# RoboArm_Schematic.net
KiCad netlist of a schematic drawn in EAGLE
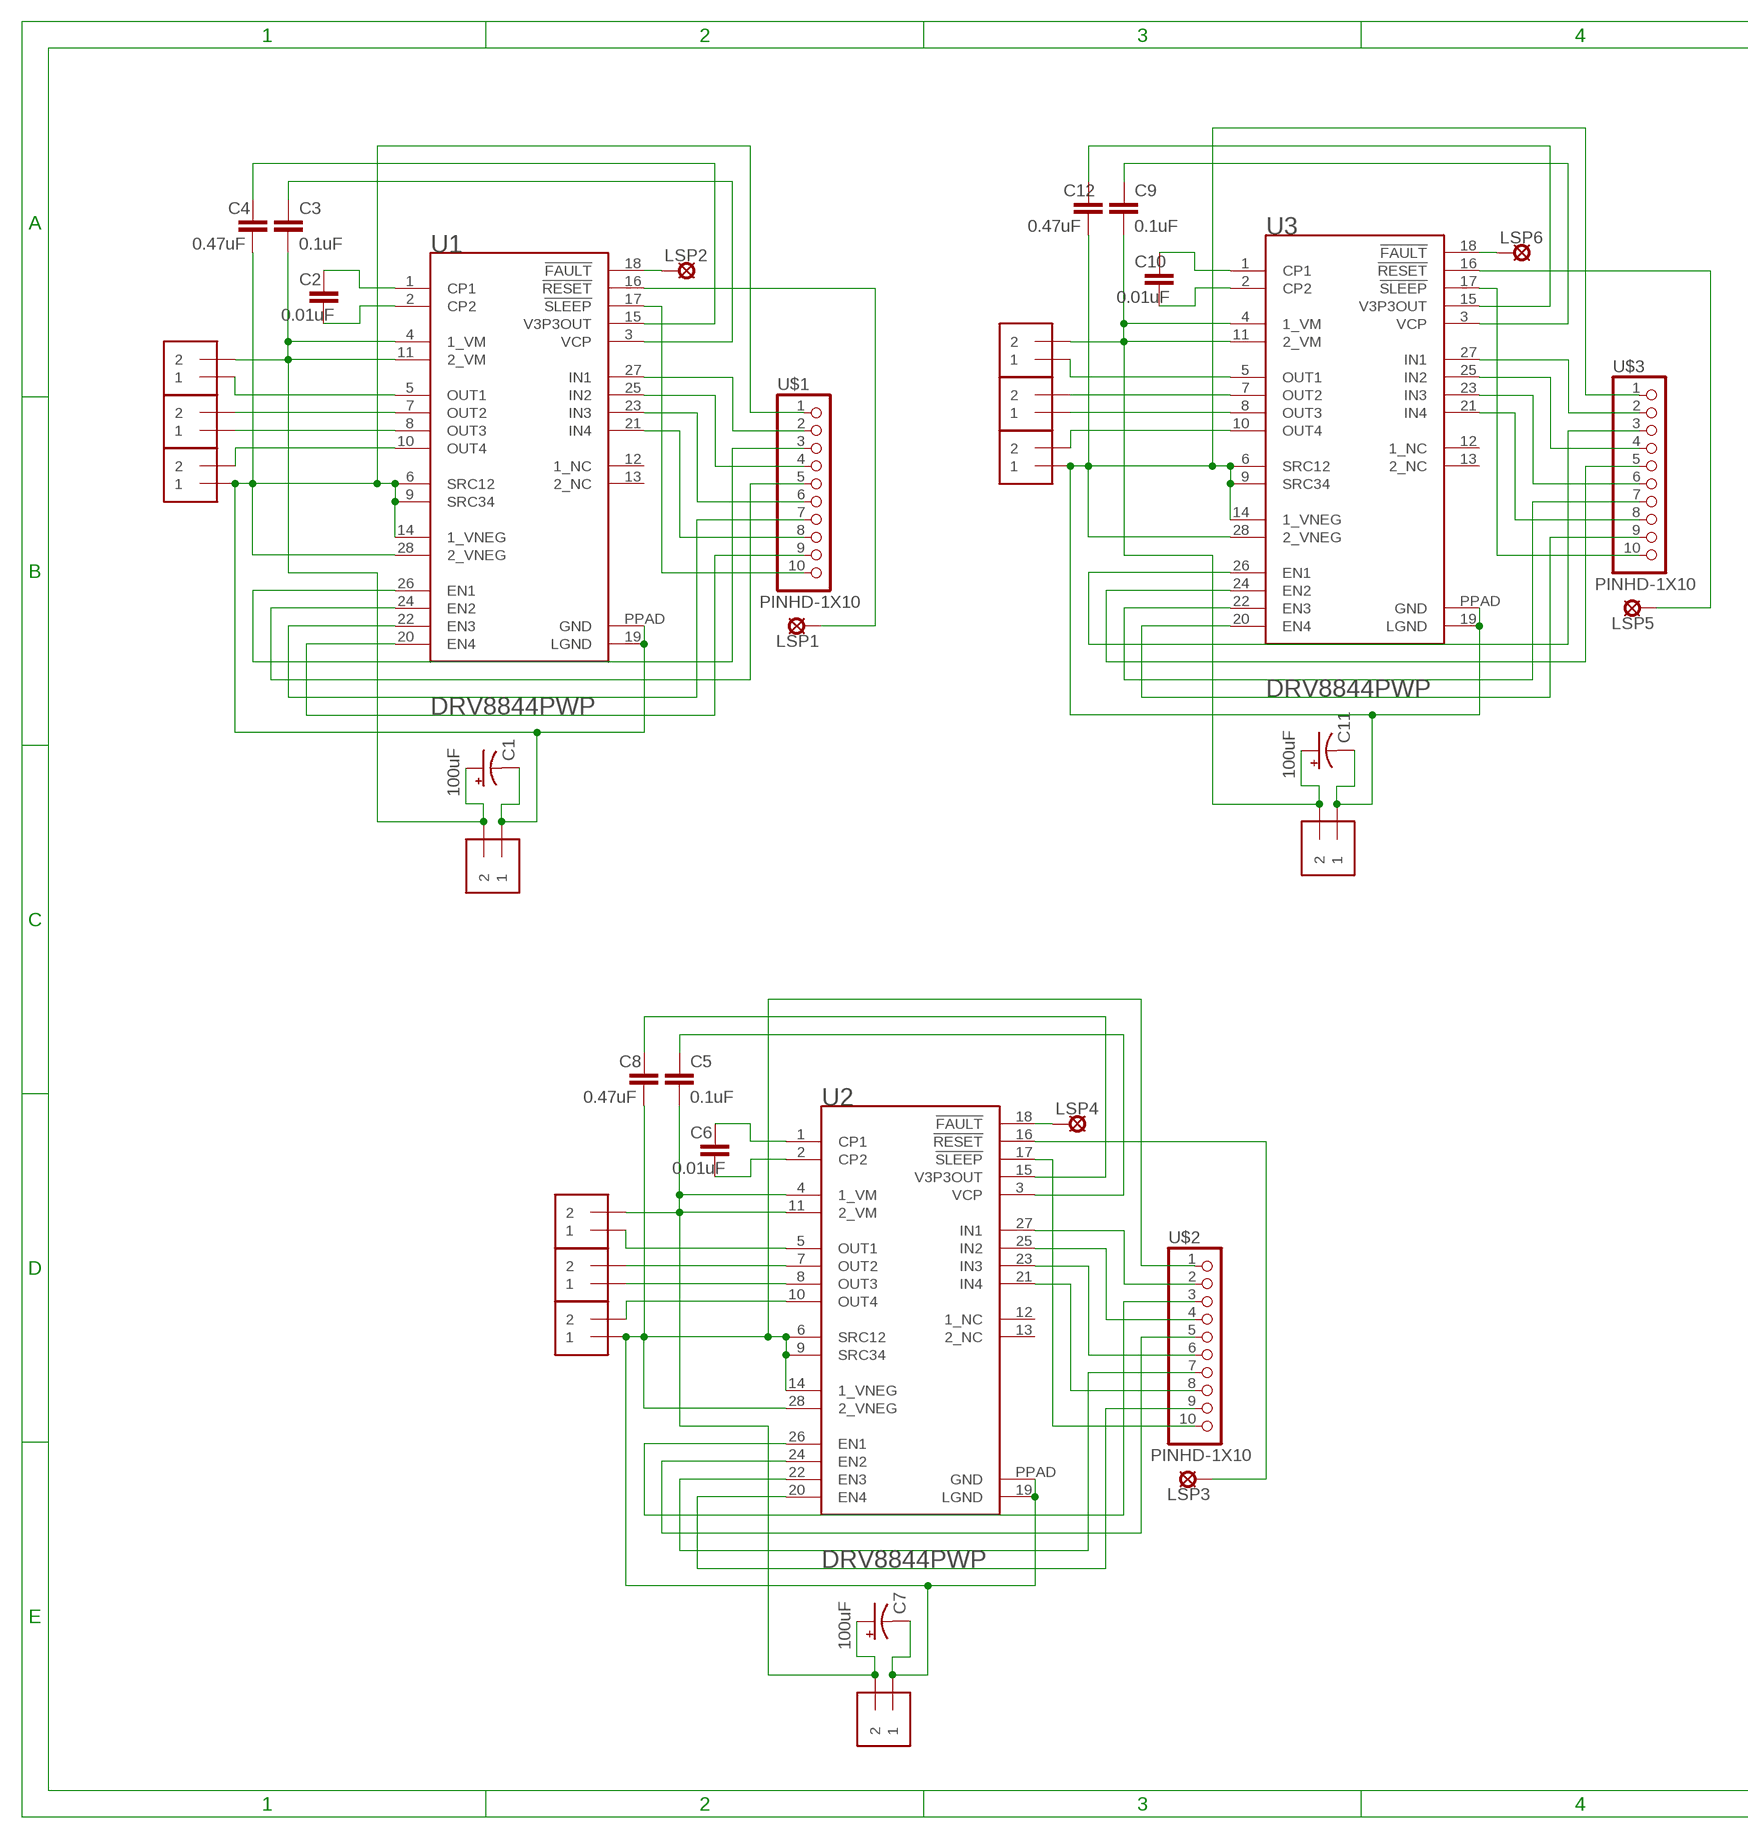
[diagram p0: schematic, sheet 1, part 1 of 2]
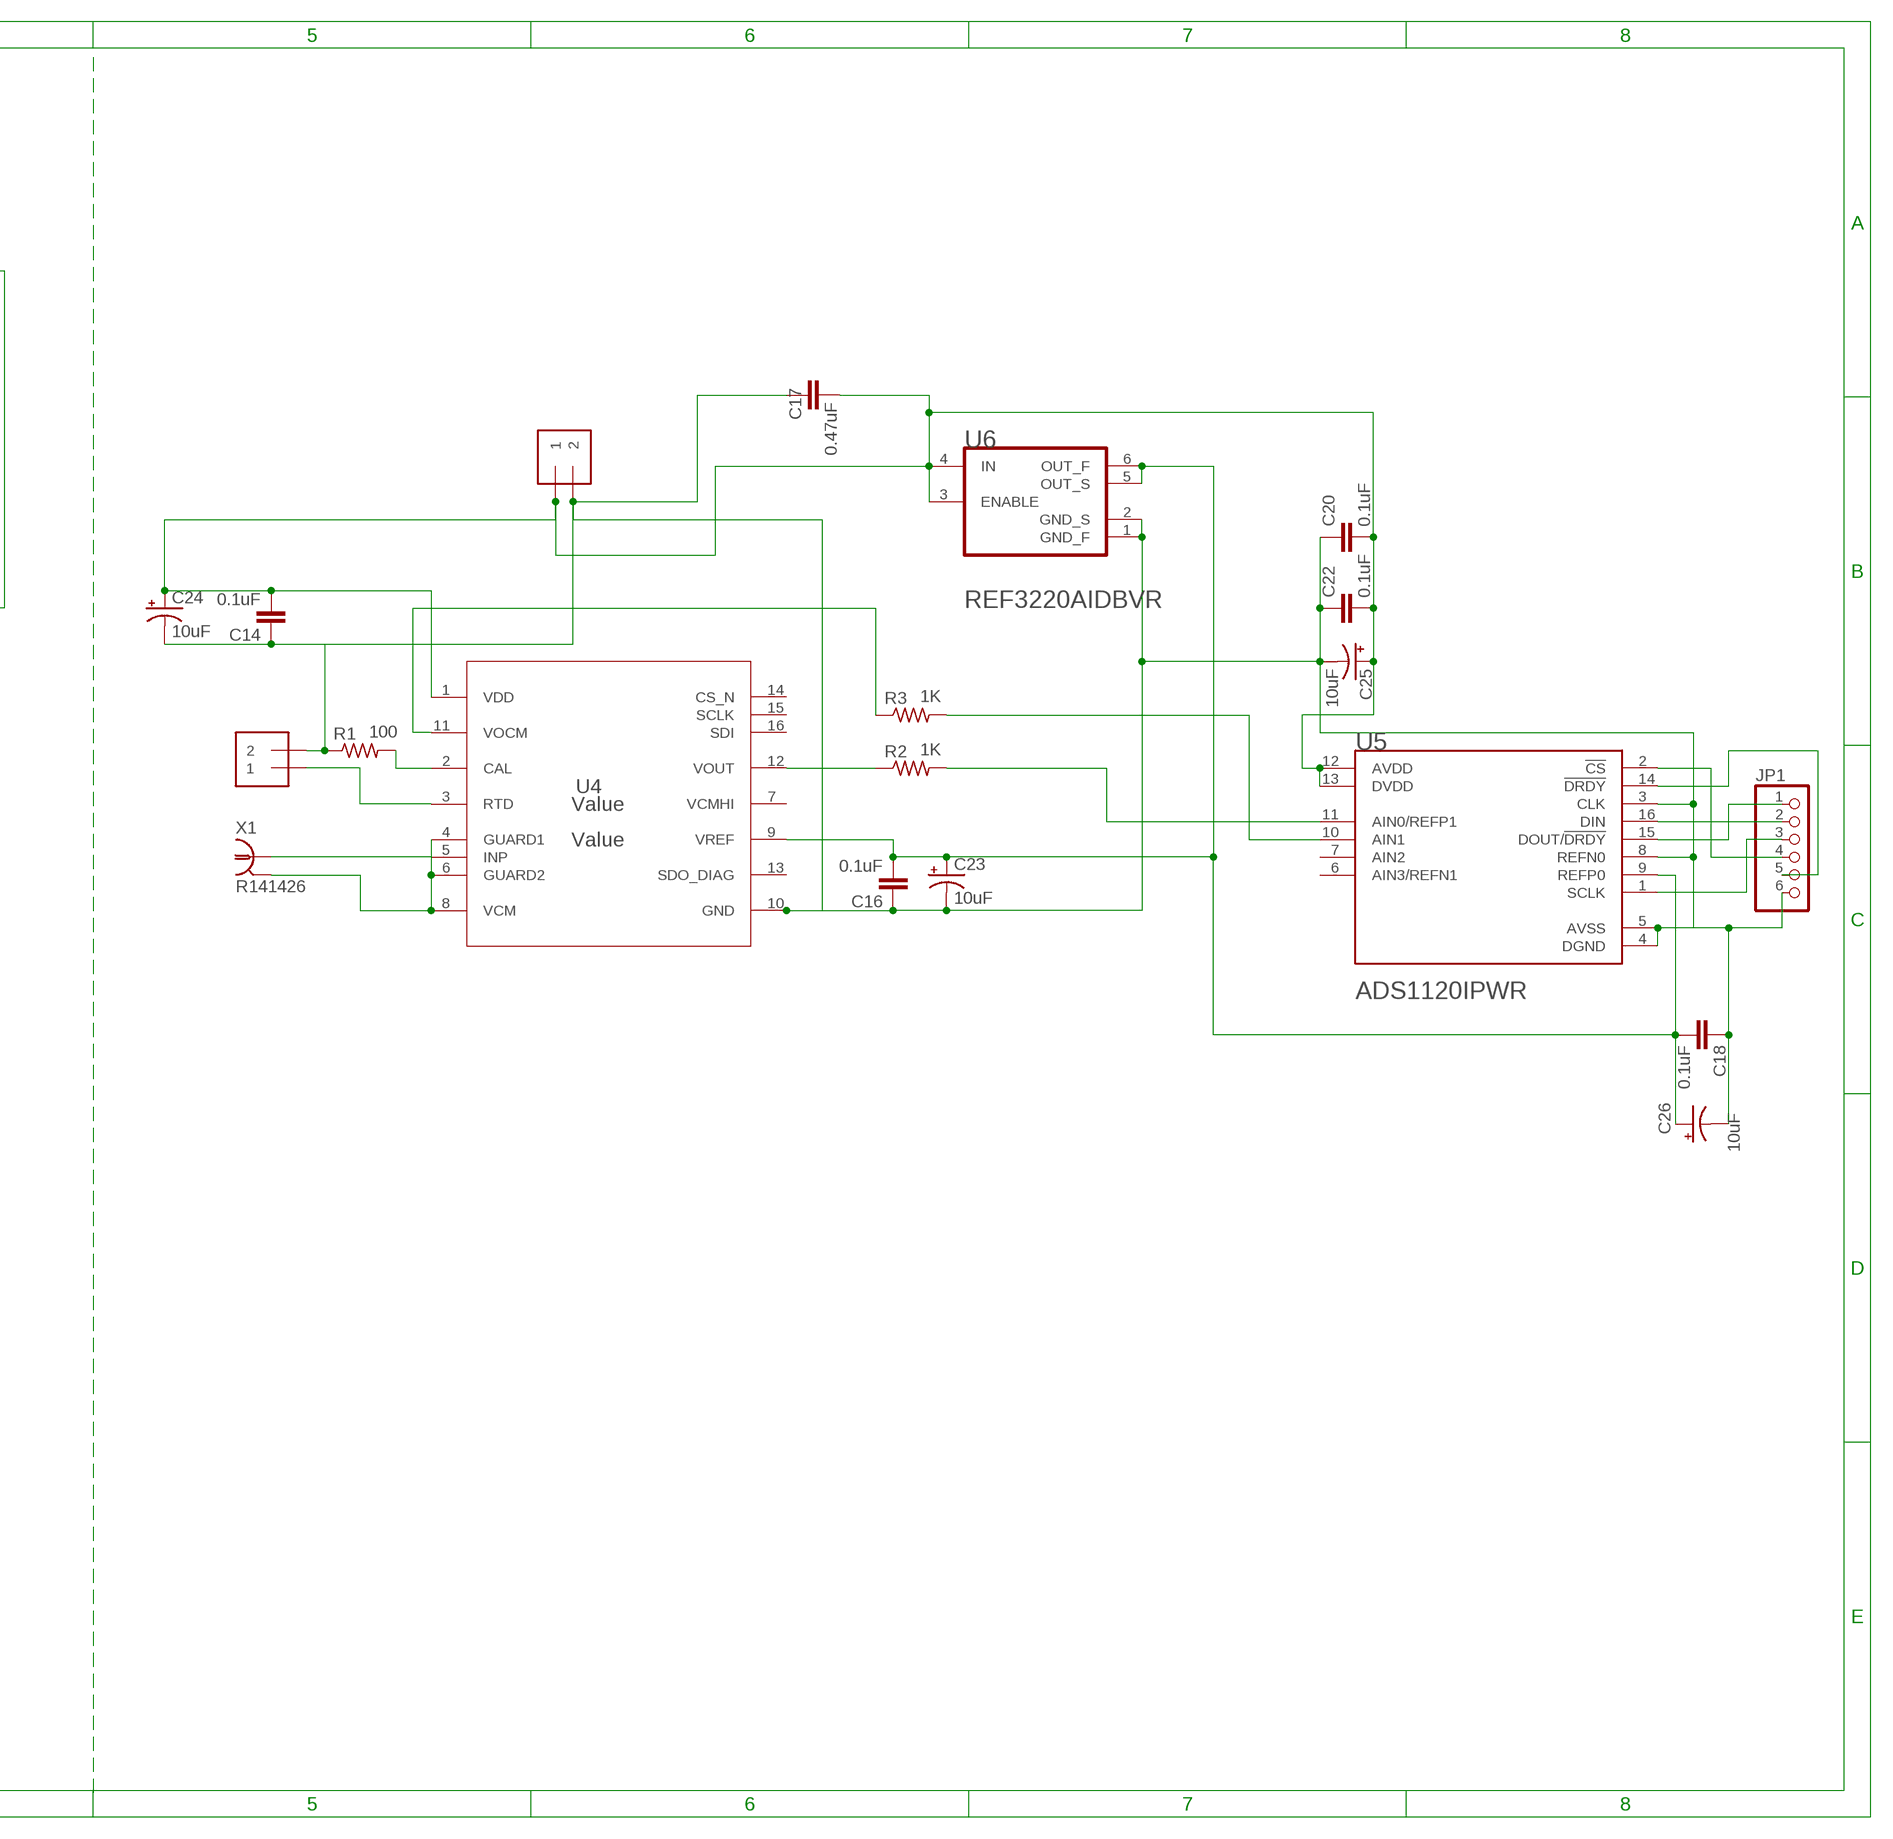
[diagram p1: schematic, sheet 1, part 2 of 2]

(export (version "E")
  (design (tool "Eeschema 10.0.6"))
  (components
    (comp (ref "C1")
      (value "100uF")
      (footprint "eagle-import:E5-8,5")
      (libsource (lib "eagle-import") (part "CPOL-USE5-8.5"))
    )
    (comp (ref "C2")
      (value "0.01uF")
      (footprint "eagle-import:C0805")
      (libsource (lib "eagle-import") (part "C-EUC0805"))
    )
    (comp (ref "C3")
      (value "0.1uF")
      (footprint "eagle-import:C0805")
      (libsource (lib "eagle-import") (part "C-EUC0805"))
    )
    (comp (ref "C4")
      (value "0.47uF")
      (footprint "eagle-import:C0805")
      (libsource (lib "eagle-import") (part "C-EUC0805"))
    )
    (comp (ref "C5")
      (value "0.1uF")
      (footprint "eagle-import:C0805")
      (libsource (lib "eagle-import") (part "C-EUC0805"))
    )
    (comp (ref "C6")
      (value "0.01uF")
      (footprint "eagle-import:C0805")
      (libsource (lib "eagle-import") (part "C-EUC0805"))
    )
    (comp (ref "C7")
      (value "100uF")
      (footprint "eagle-import:E5-8,5")
      (libsource (lib "eagle-import") (part "CPOL-USE5-8.5"))
    )
    (comp (ref "C8")
      (value "0.47uF")
      (footprint "eagle-import:C0805")
      (libsource (lib "eagle-import") (part "C-EUC0805"))
    )
    (comp (ref "C9")
      (value "0.1uF")
      (footprint "eagle-import:C0805")
      (libsource (lib "eagle-import") (part "C-EUC0805"))
    )
    (comp (ref "C10")
      (value "0.01uF")
      (footprint "eagle-import:C0805")
      (libsource (lib "eagle-import") (part "C-EUC0805"))
    )
    (comp (ref "C11")
      (value "100uF")
      (footprint "eagle-import:E5-8,5")
      (libsource (lib "eagle-import") (part "CPOL-USE5-8.5"))
    )
    (comp (ref "C12")
      (value "0.47uF")
      (footprint "eagle-import:C0805")
      (libsource (lib "eagle-import") (part "C-EUC0805"))
    )
    (comp (ref "C14")
      (value "0.1uF")
      (footprint "eagle-import:C0805")
      (libsource (lib "eagle-import") (part "C-EUC0805"))
    )
    (comp (ref "C16")
      (value "0.1uF")
      (footprint "eagle-import:C0805")
      (libsource (lib "eagle-import") (part "C-EUC0805"))
    )
    (comp (ref "C17")
      (value "0.47uF")
      (footprint "eagle-import:C0805")
      (libsource (lib "eagle-import") (part "C-EUC0805"))
    )
    (comp (ref "C18")
      (value "0.1uF")
      (footprint "eagle-import:C0805")
      (libsource (lib "eagle-import") (part "C-EUC0805"))
    )
    (comp (ref "C20")
      (value "0.1uF")
      (footprint "eagle-import:C0805")
      (libsource (lib "eagle-import") (part "C-EUC0805"))
    )
    (comp (ref "C22")
      (value "0.1uF")
      (footprint "eagle-import:C0805")
      (libsource (lib "eagle-import") (part "C-EUC0805"))
    )
    (comp (ref "C23")
      (value "10uF")
      (footprint "eagle-import:E2-4")
      (libsource (lib "eagle-import") (part "CPOL-USE2-4"))
    )
    (comp (ref "C24")
      (value "10uF")
      (footprint "eagle-import:E2-4")
      (libsource (lib "eagle-import") (part "CPOL-USE2-4"))
    )
    (comp (ref "C25")
      (value "10uF")
      (footprint "eagle-import:E2-4")
      (libsource (lib "eagle-import") (part "CPOL-USE2-4"))
    )
    (comp (ref "C26")
      (value "10uF")
      (footprint "eagle-import:E2-4")
      (libsource (lib "eagle-import") (part "CPOL-USE2-4"))
    )
    (comp (ref "J1")
      (value "1X2-3.5MM")
      (footprint "eagle-import:1X2-3.5MM")
      (libsource (lib "eagle-import") (part "1X2-3.5MM"))
    )
    (comp (ref "J2")
      (value "1X2-3.5MM")
      (footprint "eagle-import:1X2-3.5MM")
      (libsource (lib "eagle-import") (part "1X2-3.5MM"))
    )
    (comp (ref "J3")
      (value "1X2-3.5MM")
      (footprint "eagle-import:1X2-3.5MM")
      (libsource (lib "eagle-import") (part "1X2-3.5MM"))
    )
    (comp (ref "J4")
      (value "1X2-3.5MM")
      (footprint "eagle-import:1X2-3.5MM")
      (libsource (lib "eagle-import") (part "1X2-3.5MM"))
    )
    (comp (ref "J5")
      (value "1X2-3.5MM")
      (footprint "eagle-import:1X2-3.5MM")
      (libsource (lib "eagle-import") (part "1X2-3.5MM"))
    )
    (comp (ref "J6")
      (value "1X2-3.5MM")
      (footprint "eagle-import:1X2-3.5MM")
      (libsource (lib "eagle-import") (part "1X2-3.5MM"))
    )
    (comp (ref "J7")
      (value "1X2-3.5MM")
      (footprint "eagle-import:1X2-3.5MM")
      (libsource (lib "eagle-import") (part "1X2-3.5MM"))
    )
    (comp (ref "J8")
      (value "1X2-3.5MM")
      (footprint "eagle-import:1X2-3.5MM")
      (libsource (lib "eagle-import") (part "1X2-3.5MM"))
    )
    (comp (ref "J9")
      (value "1X2-3.5MM")
      (footprint "eagle-import:1X2-3.5MM")
      (libsource (lib "eagle-import") (part "1X2-3.5MM"))
    )
    (comp (ref "J10")
      (value "1X2-3.5MM")
      (footprint "eagle-import:1X2-3.5MM")
      (libsource (lib "eagle-import") (part "1X2-3.5MM"))
    )
    (comp (ref "J11")
      (value "1X2-3.5MM")
      (footprint "eagle-import:1X2-3.5MM")
      (libsource (lib "eagle-import") (part "1X2-3.5MM"))
    )
    (comp (ref "J12")
      (value "1X2-3.5MM")
      (footprint "eagle-import:1X2-3.5MM")
      (libsource (lib "eagle-import") (part "1X2-3.5MM"))
    )
    (comp (ref "J13")
      (value "1X2-3.5MM")
      (footprint "eagle-import:1X2-3.5MM")
      (libsource (lib "eagle-import") (part "1X2-3.5MM"))
    )
    (comp (ref "J15")
      (value "1X2-3.5MM")
      (footprint "eagle-import:1X2-3.5MM")
      (libsource (lib "eagle-import") (part "1X2-3.5MM"))
    )
    (comp (ref "JP1")
      (value "PINHD-1X6")
      (footprint "eagle-import:1X06")
      (libsource (lib "eagle-import") (part "PINHD-1X6"))
    )
    (comp (ref "LSP1")
      (value "SE11")
      (footprint "eagle-import:SE11")
      (libsource (lib "eagle-import") (part "SE11"))
    )
    (comp (ref "LSP2")
      (value "SE11")
      (footprint "eagle-import:SE11")
      (libsource (lib "eagle-import") (part "SE11"))
    )
    (comp (ref "LSP3")
      (value "SE11")
      (footprint "eagle-import:SE11")
      (libsource (lib "eagle-import") (part "SE11"))
    )
    (comp (ref "LSP4")
      (value "SE11")
      (footprint "eagle-import:SE11")
      (libsource (lib "eagle-import") (part "SE11"))
    )
    (comp (ref "LSP5")
      (value "SE11")
      (footprint "eagle-import:SE11")
      (libsource (lib "eagle-import") (part "SE11"))
    )
    (comp (ref "LSP6")
      (value "SE11")
      (footprint "eagle-import:SE11")
      (libsource (lib "eagle-import") (part "SE11"))
    )
    (comp (ref "R1")
      (value "100")
      (footprint "eagle-import:M0805")
      (libsource (lib "eagle-import") (part "R-US_M0805"))
    )
    (comp (ref "R2")
      (value "1K")
      (footprint "eagle-import:M0805")
      (libsource (lib "eagle-import") (part "R-US_M0805"))
    )
    (comp (ref "R3")
      (value "1K")
      (footprint "eagle-import:M0805")
      (libsource (lib "eagle-import") (part "R-US_M0805"))
    )
    (comp (ref "U$1")
      (value "PINHD-1X10")
      (footprint "eagle-import:1X10-BIG")
      (libsource (lib "eagle-import") (part "PINHD-1X10"))
    )
    (comp (ref "U$2")
      (value "PINHD-1X10")
      (footprint "eagle-import:1X10-BIG")
      (libsource (lib "eagle-import") (part "PINHD-1X10"))
    )
    (comp (ref "U$3")
      (value "PINHD-1X10")
      (footprint "eagle-import:1X10-BIG")
      (libsource (lib "eagle-import") (part "PINHD-1X10"))
    )
    (comp (ref "U1")
      (value "TEXAS_INSTRUMENTS_DRV8844PWPTEXAS_INSTRUMENTS_DRV8844PWP_0_0")
      (footprint "eagle-import:TEXAS_INSTRUMENTS_DRV8844PWP_0")
      (fields
        (field (name "DIGIKEY_PART_NUMBER") "296-46510-5-ND")
        (field (name "MF") "Texas Instruments")
        (field (name "MOUSER_PART_NUMBER") "595-DRV8844PWP")
      )
      (libsource (lib "eagle-import") (part "TEXAS_INSTRUMENTS_DRV8844PWPTEXAS_INSTRUMENTS_DRV8844PWP_0_0"))
    )
    (comp (ref "U2")
      (value "TEXAS_INSTRUMENTS_DRV8844PWPTEXAS_INSTRUMENTS_DRV8844PWP_0_0")
      (footprint "eagle-import:TEXAS_INSTRUMENTS_DRV8844PWP_0")
      (fields
        (field (name "DIGIKEY_PART_NUMBER") "296-46510-5-ND")
        (field (name "MF") "Texas Instruments")
        (field (name "MOUSER_PART_NUMBER") "595-DRV8844PWP")
      )
      (libsource (lib "eagle-import") (part "TEXAS_INSTRUMENTS_DRV8844PWPTEXAS_INSTRUMENTS_DRV8844PWP_0_0"))
    )
    (comp (ref "U3")
      (value "TEXAS_INSTRUMENTS_DRV8844PWPTEXAS_INSTRUMENTS_DRV8844PWP_0_0")
      (footprint "eagle-import:TEXAS_INSTRUMENTS_DRV8844PWP_0")
      (fields
        (field (name "DIGIKEY_PART_NUMBER") "296-46510-5-ND")
        (field (name "MF") "Texas Instruments")
        (field (name "MOUSER_PART_NUMBER") "595-DRV8844PWP")
      )
      (libsource (lib "eagle-import") (part "TEXAS_INSTRUMENTS_DRV8844PWPTEXAS_INSTRUMENTS_DRV8844PWP_0_0"))
    )
    (comp (ref "U4")
      (value "Value")
      (footprint "eagle-import:PW0016A_L")
      (fields
        (field (name "ALTERNATE_PARTNUMBER") "LMP91200MT/NOPB")
        (field (name "MANUFACTURER") "Texas Instruments")
        (field (name "PARTNUMBER") "LMP91200MTX/NOPB")
      )
      (libsource (lib "eagle-import") (part "LMP91200MT/NOPBPW0016A_L"))
    )
    (comp (ref "U5")
      (value "TEXAS_INSTRUMENTS_ADS1120IPWRTEXAS_INSTRUMENTS_ADS1120IPWR_0_0")
      (footprint "eagle-import:TEXAS_INSTRUMENTS_ADS1120IPWR_0")
      (fields
        (field (name "DIGIKEY_PART_NUMBER") "296-37280-1-ND")
        (field (name "MF") "Texas Instruments")
        (field (name "MOUSER_PART_NUMBER") "595-ADS1120IPWR")
      )
      (libsource (lib "eagle-import") (part "TEXAS_INSTRUMENTS_ADS1120IPWRTEXAS_INSTRUMENTS_ADS1120IPWR_0_0"))
    )
    (comp (ref "U6")
      (value "TEXAS_INSTRUMENTS_REF3220AIDBVRTEXAS_INSTRUMENTS_REF3220AIDBVR_0_1")
      (footprint "eagle-import:TEXAS_INSTRUMENTS_REF3220AIDBVR_1")
      (fields (field (name "MF") "Texas Instruments") (field (name "MPN") "REF3220AIDBVR"))
      (libsource (lib "eagle-import") (part "TEXAS_INSTRUMENTS_REF3220AIDBVRTEXAS_INSTRUMENTS_REF3220AIDBVR_0_1"))
    )
    (comp (ref "X1")
      (value "R141426")
      (footprint "eagle-import:R141426")
      (fields (field (name "MF") "FARNELL") (field (name "MPN") "R141426161"))
      (libsource (lib "eagle-import") (part "R141426"))
    )
  )
  (nets
    (net (code "1") (name "Net-(U1-1_VM)") (class "Default")
      (node (ref "C1") (pin "+") (pinfunction "+_+") (pintype "passive"))
      (node (ref "C3") (pin "2") (pinfunction "2_2") (pintype "passive"))
      (node (ref "J1") (pin "2") (pinfunction "2_2") (pintype "passive"))
      (node (ref "J2") (pin "2") (pinfunction "2_2") (pintype "passive"))
      (node (ref "U1") (pin "11") (pinfunction "2_VM_11") (pintype "power_in"))
      (node (ref "U1") (pin "4") (pinfunction "1_VM_4") (pintype "power_in"))
    )
    (net (code "2") (name "Net-(U1-1_VNEG)") (class "Default")
      (node (ref "C1") (pin "-") (pinfunction "-_-") (pintype "passive"))
      (node (ref "C4") (pin "2") (pinfunction "2_2") (pintype "passive"))
      (node (ref "J1") (pin "1") (pinfunction "1_1") (pintype "passive"))
      (node (ref "J4") (pin "1") (pinfunction "1_1") (pintype "passive"))
      (node (ref "U$1") (pin "1") (pinfunction "1_1") (pintype "passive"))
      (node (ref "U1") (pin "14") (pinfunction "1_VNEG_14") (pintype "power_in"))
      (node (ref "U1") (pin "19") (pinfunction "LGND_19") (pintype "power_in"))
      (node (ref "U1") (pin "28") (pinfunction "2_VNEG_28") (pintype "power_in"))
      (node (ref "U1") (pin "6") (pinfunction "SRC12_6") (pintype "power_in"))
      (node (ref "U1") (pin "9") (pinfunction "SRC34_9") (pintype "power_in"))
      (node (ref "U1") (pin "PPAD") (pinfunction "GND_PPAD") (pintype "power_in"))
    )
    (net (code "3") (name "Net-(U1-CP1)") (class "Default")
      (node (ref "C2") (pin "1") (pinfunction "1_1") (pintype "passive"))
      (node (ref "U1") (pin "1") (pinfunction "CP1_1") (pintype "power_in"))
    )
    (net (code "4") (name "Net-(U1-CP2)") (class "Default")
      (node (ref "C2") (pin "2") (pinfunction "2_2") (pintype "passive"))
      (node (ref "U1") (pin "2") (pinfunction "CP2_2") (pintype "power_in"))
    )
    (net (code "5") (name "Net-(U1-EN1)") (class "Default")
      (node (ref "U$1") (pin "3") (pinfunction "3_3") (pintype "passive"))
      (node (ref "U1") (pin "26") (pinfunction "EN1_26") (pintype "input"))
    )
    (net (code "6") (name "Net-(U1-EN2)") (class "Default")
      (node (ref "U$1") (pin "5") (pinfunction "5_5") (pintype "passive"))
      (node (ref "U1") (pin "24") (pinfunction "EN2_24") (pintype "input"))
    )
    (net (code "7") (name "Net-(U1-EN3)") (class "Default")
      (node (ref "U$1") (pin "7") (pinfunction "7_7") (pintype "passive"))
      (node (ref "U1") (pin "22") (pinfunction "EN3_22") (pintype "input"))
    )
    (net (code "8") (name "Net-(U1-EN4)") (class "Default")
      (node (ref "U$1") (pin "9") (pinfunction "9_9") (pintype "passive"))
      (node (ref "U1") (pin "20") (pinfunction "EN4_20") (pintype "input"))
    )
    (net (code "9") (name "Net-(U1-IN1)") (class "Default")
      (node (ref "U$1") (pin "2") (pinfunction "2_2") (pintype "passive"))
      (node (ref "U1") (pin "27") (pinfunction "IN1_27") (pintype "input"))
    )
    (net (code "10") (name "Net-(U1-IN2)") (class "Default")
      (node (ref "U$1") (pin "4") (pinfunction "4_4") (pintype "passive"))
      (node (ref "U1") (pin "25") (pinfunction "IN2_25") (pintype "input"))
    )
    (net (code "11") (name "Net-(U1-IN3)") (class "Default")
      (node (ref "U$1") (pin "6") (pinfunction "6_6") (pintype "passive"))
      (node (ref "U1") (pin "23") (pinfunction "IN3_23") (pintype "input"))
    )
    (net (code "12") (name "Net-(U1-IN4)") (class "Default")
      (node (ref "U$1") (pin "8") (pinfunction "8_8") (pintype "passive"))
      (node (ref "U1") (pin "21") (pinfunction "IN4_21") (pintype "input"))
    )
    (net (code "13") (name "Net-(U1-OUT1)") (class "Default")
      (node (ref "J2") (pin "1") (pinfunction "1_1") (pintype "passive"))
      (node (ref "U1") (pin "5") (pinfunction "OUT1_5") (pintype "output"))
    )
    (net (code "14") (name "Net-(U1-OUT2)") (class "Default")
      (node (ref "J3") (pin "2") (pinfunction "2_2") (pintype "passive"))
      (node (ref "U1") (pin "7") (pinfunction "OUT2_7") (pintype "output"))
    )
    (net (code "15") (name "Net-(U1-OUT3)") (class "Default")
      (node (ref "J3") (pin "1") (pinfunction "1_1") (pintype "passive"))
      (node (ref "U1") (pin "8") (pinfunction "OUT3_8") (pintype "output"))
    )
    (net (code "16") (name "Net-(U1-OUT4)") (class "Default")
      (node (ref "J4") (pin "2") (pinfunction "2_2") (pintype "passive"))
      (node (ref "U1") (pin "10") (pinfunction "OUT4_10") (pintype "output"))
    )
    (net (code "17") (name "Net-(U1-V3P3OUT)") (class "Default")
      (node (ref "C4") (pin "1") (pinfunction "1_1") (pintype "passive"))
      (node (ref "U1") (pin "15") (pinfunction "V3P3OUT_15") (pintype "power_in"))
    )
    (net (code "18") (name "Net-(U1-VCP)") (class "Default")
      (node (ref "C3") (pin "1") (pinfunction "1_1") (pintype "passive"))
      (node (ref "U1") (pin "3") (pinfunction "VCP_3") (pintype "power_in"))
    )
    (net (code "19") (name "Net-(U1-~{FAULT})") (class "Default")
      (node (ref "LSP2") (pin "MP") (pinfunction "MP_MP") (pintype "passive"))
      (node (ref "U1") (pin "18") (pinfunction "~{FAULT}_18") (pintype "output"))
    )
    (net (code "20") (name "Net-(U1-~{RESET})") (class "Default")
      (node (ref "LSP1") (pin "MP") (pinfunction "MP_MP") (pintype "passive"))
      (node (ref "U1") (pin "16") (pinfunction "~{RESET}_16") (pintype "input"))
    )
    (net (code "21") (name "Net-(U1-~{SLEEP})") (class "Default")
      (node (ref "U$1") (pin "10") (pinfunction "10_10") (pintype "passive"))
      (node (ref "U1") (pin "17") (pinfunction "~{SLEEP}_17") (pintype "input"))
    )
    (net (code "22") (name "Net-(U2-1_VM)") (class "Default")
      (node (ref "C5") (pin "2") (pinfunction "2_2") (pintype "passive"))
      (node (ref "C7") (pin "+") (pinfunction "+_+") (pintype "passive"))
      (node (ref "J5") (pin "2") (pinfunction "2_2") (pintype "passive"))
      (node (ref "J6") (pin "2") (pinfunction "2_2") (pintype "passive"))
      (node (ref "U2") (pin "11") (pinfunction "2_VM_11") (pintype "power_in"))
      (node (ref "U2") (pin "4") (pinfunction "1_VM_4") (pintype "power_in"))
    )
    (net (code "23") (name "Net-(U2-1_VNEG)") (class "Default")
      (node (ref "C7") (pin "-") (pinfunction "-_-") (pintype "passive"))
      (node (ref "C8") (pin "2") (pinfunction "2_2") (pintype "passive"))
      (node (ref "J5") (pin "1") (pinfunction "1_1") (pintype "passive"))
      (node (ref "J8") (pin "1") (pinfunction "1_1") (pintype "passive"))
      (node (ref "U$2") (pin "1") (pinfunction "1_1") (pintype "passive"))
      (node (ref "U2") (pin "14") (pinfunction "1_VNEG_14") (pintype "power_in"))
      (node (ref "U2") (pin "19") (pinfunction "LGND_19") (pintype "power_in"))
      (node (ref "U2") (pin "28") (pinfunction "2_VNEG_28") (pintype "power_in"))
      (node (ref "U2") (pin "6") (pinfunction "SRC12_6") (pintype "power_in"))
      (node (ref "U2") (pin "9") (pinfunction "SRC34_9") (pintype "power_in"))
      (node (ref "U2") (pin "PPAD") (pinfunction "GND_PPAD") (pintype "power_in"))
    )
    (net (code "24") (name "Net-(U2-CP1)") (class "Default")
      (node (ref "C6") (pin "1") (pinfunction "1_1") (pintype "passive"))
      (node (ref "U2") (pin "1") (pinfunction "CP1_1") (pintype "power_in"))
    )
    (net (code "25") (name "Net-(U2-CP2)") (class "Default")
      (node (ref "C6") (pin "2") (pinfunction "2_2") (pintype "passive"))
      (node (ref "U2") (pin "2") (pinfunction "CP2_2") (pintype "power_in"))
    )
    (net (code "26") (name "Net-(U2-EN1)") (class "Default")
      (node (ref "U$2") (pin "3") (pinfunction "3_3") (pintype "passive"))
      (node (ref "U2") (pin "26") (pinfunction "EN1_26") (pintype "input"))
    )
    (net (code "27") (name "Net-(U2-EN2)") (class "Default")
      (node (ref "U$2") (pin "5") (pinfunction "5_5") (pintype "passive"))
      (node (ref "U2") (pin "24") (pinfunction "EN2_24") (pintype "input"))
    )
    (net (code "28") (name "Net-(U2-EN3)") (class "Default")
      (node (ref "U$2") (pin "7") (pinfunction "7_7") (pintype "passive"))
      (node (ref "U2") (pin "22") (pinfunction "EN3_22") (pintype "input"))
    )
    (net (code "29") (name "Net-(U2-EN4)") (class "Default")
      (node (ref "U$2") (pin "9") (pinfunction "9_9") (pintype "passive"))
      (node (ref "U2") (pin "20") (pinfunction "EN4_20") (pintype "input"))
    )
    (net (code "30") (name "Net-(U2-IN1)") (class "Default")
      (node (ref "U$2") (pin "2") (pinfunction "2_2") (pintype "passive"))
      (node (ref "U2") (pin "27") (pinfunction "IN1_27") (pintype "input"))
    )
    (net (code "31") (name "Net-(U2-IN2)") (class "Default")
      (node (ref "U$2") (pin "4") (pinfunction "4_4") (pintype "passive"))
      (node (ref "U2") (pin "25") (pinfunction "IN2_25") (pintype "input"))
    )
    (net (code "32") (name "Net-(U2-IN3)") (class "Default")
      (node (ref "U$2") (pin "6") (pinfunction "6_6") (pintype "passive"))
      (node (ref "U2") (pin "23") (pinfunction "IN3_23") (pintype "input"))
    )
    (net (code "33") (name "Net-(U2-IN4)") (class "Default")
      (node (ref "U$2") (pin "8") (pinfunction "8_8") (pintype "passive"))
      (node (ref "U2") (pin "21") (pinfunction "IN4_21") (pintype "input"))
    )
    (net (code "34") (name "Net-(U2-OUT1)") (class "Default")
      (node (ref "J6") (pin "1") (pinfunction "1_1") (pintype "passive"))
      (node (ref "U2") (pin "5") (pinfunction "OUT1_5") (pintype "output"))
    )
    (net (code "35") (name "Net-(U2-OUT2)") (class "Default")
      (node (ref "J7") (pin "2") (pinfunction "2_2") (pintype "passive"))
      (node (ref "U2") (pin "7") (pinfunction "OUT2_7") (pintype "output"))
    )
    (net (code "36") (name "Net-(U2-OUT3)") (class "Default")
      (node (ref "J7") (pin "1") (pinfunction "1_1") (pintype "passive"))
      (node (ref "U2") (pin "8") (pinfunction "OUT3_8") (pintype "output"))
    )
    (net (code "37") (name "Net-(U2-OUT4)") (class "Default")
      (node (ref "J8") (pin "2") (pinfunction "2_2") (pintype "passive"))
      (node (ref "U2") (pin "10") (pinfunction "OUT4_10") (pintype "output"))
    )
    (net (code "38") (name "Net-(U2-V3P3OUT)") (class "Default")
      (node (ref "C8") (pin "1") (pinfunction "1_1") (pintype "passive"))
      (node (ref "U2") (pin "15") (pinfunction "V3P3OUT_15") (pintype "power_in"))
    )
    (net (code "39") (name "Net-(U2-VCP)") (class "Default")
      (node (ref "C5") (pin "1") (pinfunction "1_1") (pintype "passive"))
      (node (ref "U2") (pin "3") (pinfunction "VCP_3") (pintype "power_in"))
    )
    (net (code "40") (name "Net-(U2-~{FAULT})") (class "Default")
      (node (ref "LSP4") (pin "MP") (pinfunction "MP_MP") (pintype "passive"))
      (node (ref "U2") (pin "18") (pinfunction "~{FAULT}_18") (pintype "output"))
    )
    (net (code "41") (name "Net-(U2-~{RESET})") (class "Default")
      (node (ref "LSP3") (pin "MP") (pinfunction "MP_MP") (pintype "passive"))
      (node (ref "U2") (pin "16") (pinfunction "~{RESET}_16") (pintype "input"))
    )
    (net (code "42") (name "Net-(U2-~{SLEEP})") (class "Default")
      (node (ref "U$2") (pin "10") (pinfunction "10_10") (pintype "passive"))
      (node (ref "U2") (pin "17") (pinfunction "~{SLEEP}_17") (pintype "input"))
    )
    (net (code "43") (name "Net-(U3-1_VM)") (class "Default")
      (node (ref "C11") (pin "+") (pinfunction "+_+") (pintype "passive"))
      (node (ref "C9") (pin "2") (pinfunction "2_2") (pintype "passive"))
      (node (ref "J10") (pin "2") (pinfunction "2_2") (pintype "passive"))
      (node (ref "J9") (pin "2") (pinfunction "2_2") (pintype "passive"))
      (node (ref "U3") (pin "11") (pinfunction "2_VM_11") (pintype "power_in"))
      (node (ref "U3") (pin "4") (pinfunction "1_VM_4") (pintype "power_in"))
    )
    (net (code "44") (name "Net-(U3-1_VNEG)") (class "Default")
      (node (ref "C11") (pin "-") (pinfunction "-_-") (pintype "passive"))
      (node (ref "C12") (pin "2") (pinfunction "2_2") (pintype "passive"))
      (node (ref "J12") (pin "1") (pinfunction "1_1") (pintype "passive"))
      (node (ref "J9") (pin "1") (pinfunction "1_1") (pintype "passive"))
      (node (ref "U$3") (pin "1") (pinfunction "1_1") (pintype "passive"))
      (node (ref "U3") (pin "14") (pinfunction "1_VNEG_14") (pintype "power_in"))
      (node (ref "U3") (pin "19") (pinfunction "LGND_19") (pintype "power_in"))
      (node (ref "U3") (pin "28") (pinfunction "2_VNEG_28") (pintype "power_in"))
      (node (ref "U3") (pin "6") (pinfunction "SRC12_6") (pintype "power_in"))
      (node (ref "U3") (pin "9") (pinfunction "SRC34_9") (pintype "power_in"))
      (node (ref "U3") (pin "PPAD") (pinfunction "GND_PPAD") (pintype "power_in"))
    )
    (net (code "45") (name "Net-(U3-CP1)") (class "Default")
      (node (ref "C10") (pin "1") (pinfunction "1_1") (pintype "passive"))
      (node (ref "U3") (pin "1") (pinfunction "CP1_1") (pintype "power_in"))
    )
    (net (code "46") (name "Net-(U3-CP2)") (class "Default")
      (node (ref "C10") (pin "2") (pinfunction "2_2") (pintype "passive"))
      (node (ref "U3") (pin "2") (pinfunction "CP2_2") (pintype "power_in"))
    )
    (net (code "47") (name "Net-(U3-EN1)") (class "Default")
      (node (ref "U$3") (pin "3") (pinfunction "3_3") (pintype "passive"))
      (node (ref "U3") (pin "26") (pinfunction "EN1_26") (pintype "input"))
    )
    (net (code "48") (name "Net-(U3-EN2)") (class "Default")
      (node (ref "U$3") (pin "5") (pinfunction "5_5") (pintype "passive"))
      (node (ref "U3") (pin "24") (pinfunction "EN2_24") (pintype "input"))
    )
    (net (code "49") (name "Net-(U3-EN3)") (class "Default")
      (node (ref "U$3") (pin "7") (pinfunction "7_7") (pintype "passive"))
      (node (ref "U3") (pin "22") (pinfunction "EN3_22") (pintype "input"))
    )
    (net (code "50") (name "Net-(U3-EN4)") (class "Default")
      (node (ref "U$3") (pin "9") (pinfunction "9_9") (pintype "passive"))
      (node (ref "U3") (pin "20") (pinfunction "EN4_20") (pintype "input"))
    )
    (net (code "51") (name "Net-(U3-IN1)") (class "Default")
      (node (ref "U$3") (pin "2") (pinfunction "2_2") (pintype "passive"))
      (node (ref "U3") (pin "27") (pinfunction "IN1_27") (pintype "input"))
    )
    (net (code "52") (name "Net-(U3-IN2)") (class "Default")
      (node (ref "U$3") (pin "4") (pinfunction "4_4") (pintype "passive"))
      (node (ref "U3") (pin "25") (pinfunction "IN2_25") (pintype "input"))
    )
    (net (code "53") (name "Net-(U3-IN3)") (class "Default")
      (node (ref "U$3") (pin "6") (pinfunction "6_6") (pintype "passive"))
      (node (ref "U3") (pin "23") (pinfunction "IN3_23") (pintype "input"))
    )
    (net (code "54") (name "Net-(U3-IN4)") (class "Default")
      (node (ref "U$3") (pin "8") (pinfunction "8_8") (pintype "passive"))
      (node (ref "U3") (pin "21") (pinfunction "IN4_21") (pintype "input"))
    )
    (net (code "55") (name "Net-(U3-OUT1)") (class "Default")
      (node (ref "J10") (pin "1") (pinfunction "1_1") (pintype "passive"))
      (node (ref "U3") (pin "5") (pinfunction "OUT1_5") (pintype "output"))
    )
    (net (code "56") (name "Net-(U3-OUT2)") (class "Default")
      (node (ref "J11") (pin "2") (pinfunction "2_2") (pintype "passive"))
      (node (ref "U3") (pin "7") (pinfunction "OUT2_7") (pintype "output"))
    )
    (net (code "57") (name "Net-(U3-OUT3)") (class "Default")
      (node (ref "J11") (pin "1") (pinfunction "1_1") (pintype "passive"))
      (node (ref "U3") (pin "8") (pinfunction "OUT3_8") (pintype "output"))
    )
    (net (code "58") (name "Net-(U3-OUT4)") (class "Default")
      (node (ref "J12") (pin "2") (pinfunction "2_2") (pintype "passive"))
      (node (ref "U3") (pin "10") (pinfunction "OUT4_10") (pintype "output"))
    )
    (net (code "59") (name "Net-(U3-V3P3OUT)") (class "Default")
      (node (ref "C12") (pin "1") (pinfunction "1_1") (pintype "passive"))
      (node (ref "U3") (pin "15") (pinfunction "V3P3OUT_15") (pintype "power_in"))
    )
    (net (code "60") (name "Net-(U3-VCP)") (class "Default")
      (node (ref "C9") (pin "1") (pinfunction "1_1") (pintype "passive"))
      (node (ref "U3") (pin "3") (pinfunction "VCP_3") (pintype "power_in"))
    )
    (net (code "61") (name "Net-(U3-~{FAULT})") (class "Default")
      (node (ref "LSP6") (pin "MP") (pinfunction "MP_MP") (pintype "passive"))
      (node (ref "U3") (pin "18") (pinfunction "~{FAULT}_18") (pintype "output"))
    )
    (net (code "62") (name "Net-(U3-~{RESET})") (class "Default")
      (node (ref "LSP5") (pin "MP") (pinfunction "MP_MP") (pintype "passive"))
      (node (ref "U3") (pin "16") (pinfunction "~{RESET}_16") (pintype "input"))
    )
    (net (code "63") (name "Net-(U3-~{SLEEP})") (class "Default")
      (node (ref "U$3") (pin "10") (pinfunction "10_10") (pintype "passive"))
      (node (ref "U3") (pin "17") (pinfunction "~{SLEEP}_17") (pintype "input"))
    )
    (net (code "64") (name "Net-(U4-CAL)") (class "Default")
      (node (ref "R1") (pin "2") (pinfunction "2_2") (pintype "passive"))
      (node (ref "U4") (pin "2") (pinfunction "CAL_2") (pintype "passive"))
    )
    (net (code "65") (name "Net-(U4-GND)") (class "Default")
      (node (ref "C14") (pin "1") (pinfunction "1_1") (pintype "passive"))
      (node (ref "C16") (pin "1") (pinfunction "1_1") (pintype "passive"))
      (node (ref "C17") (pin "1") (pinfunction "1_1") (pintype "passive"))
      (node (ref "C18") (pin "1") (pinfunction "1_1") (pintype "passive"))
      (node (ref "C20") (pin "1") (pinfunction "1_1") (pintype "passive"))
      (node (ref "C22") (pin "1") (pinfunction "1_1") (pintype "passive"))
      (node (ref "C23") (pin "-") (pinfunction "-_-") (pintype "passive"))
      (node (ref "C24") (pin "-") (pinfunction "-_-") (pintype "passive"))
      (node (ref "C25") (pin "-") (pinfunction "-_-") (pintype "passive"))
      (node (ref "C26") (pin "-") (pinfunction "-_-") (pintype "passive"))
      (node (ref "J13") (pin "2") (pinfunction "2_2") (pintype "passive"))
      (node (ref "J15") (pin "2") (pinfunction "2_2") (pintype "passive"))
      (node (ref "JP1") (pin "6") (pinfunction "6_6") (pintype "passive"))
      (node (ref "R1") (pin "1") (pinfunction "1_1") (pintype "passive"))
      (node (ref "U4") (pin "10") (pinfunction "GND_10") (pintype "power_in"))
      (node (ref "U5") (pin "3") (pinfunction "CLK_3") (pintype "bidirectional"))
      (node (ref "U5") (pin "4") (pinfunction "DGND_4") (pintype "bidirectional"))
      (node (ref "U5") (pin "5") (pinfunction "AVSS_5") (pintype "bidirectional"))
      (node (ref "U5") (pin "8") (pinfunction "REFN0_8") (pintype "bidirectional"))
      (node (ref "U6") (pin "1") (pinfunction "GND_F_1") (pintype "power_in"))
      (node (ref "U6") (pin "2") (pinfunction "GND_S_2") (pintype "input"))
    )
    (net (code "66") (name "Net-(U4-GUARD1)") (class "Default")
      (node (ref "U4") (pin "4") (pinfunction "GUARD1_4") (pintype "passive"))
      (node (ref "U4") (pin "6") (pinfunction "GUARD2_6") (pintype "passive"))
      (node (ref "U4") (pin "8") (pinfunction "VCM_8") (pintype "output"))
      (node (ref "X1") (pin "2") (pinfunction "2_2") (pintype "passive"))
      (node (ref "X1") (pin "3") (pinfunction "2_3") (pintype "passive"))
      (node (ref "X1") (pin "4") (pinfunction "2_4") (pintype "passive"))
      (node (ref "X1") (pin "5") (pinfunction "2_5") (pintype "passive"))
    )
    (net (code "67") (name "Net-(U4-INP)") (class "Default")
      (node (ref "U4") (pin "5") (pinfunction "INP_5") (pintype "input"))
      (node (ref "X1") (pin "1") (pinfunction "1_1") (pintype "passive"))
    )
    (net (code "68") (name "Net-(U4-RTD)") (class "Default")
      (node (ref "J13") (pin "1") (pinfunction "1_1") (pintype "passive"))
      (node (ref "U4") (pin "3") (pinfunction "RTD_3") (pintype "output"))
    )
    (net (code "69") (name "Net-(U4-VDD)") (class "Default")
      (node (ref "C14") (pin "2") (pinfunction "2_2") (pintype "passive"))
      (node (ref "C17") (pin "2") (pinfunction "2_2") (pintype "passive"))
      (node (ref "C20") (pin "2") (pinfunction "2_2") (pintype "passive"))
      (node (ref "C22") (pin "2") (pinfunction "2_2") (pintype "passive"))
      (node (ref "C24") (pin "+") (pinfunction "+_+") (pintype "passive"))
      (node (ref "C25") (pin "+") (pinfunction "+_+") (pintype "passive"))
      (node (ref "J15") (pin "1") (pinfunction "1_1") (pintype "passive"))
      (node (ref "U4") (pin "1") (pinfunction "VDD_1") (pintype "power_in"))
      (node (ref "U5") (pin "12") (pinfunction "AVDD_12") (pintype "bidirectional"))
      (node (ref "U5") (pin "13") (pinfunction "DVDD_13") (pintype "bidirectional"))
      (node (ref "U6") (pin "3") (pinfunction "ENABLE_3") (pintype "input"))
      (node (ref "U6") (pin "4") (pinfunction "IN_4") (pintype "power_in"))
    )
    (net (code "70") (name "Net-(U4-VOCM)") (class "Default")
      (node (ref "R3") (pin "1") (pinfunction "1_1") (pintype "passive"))
      (node (ref "U4") (pin "11") (pinfunction "VOCM_11") (pintype "power_in"))
    )
    (net (code "71") (name "Net-(U4-VOUT)") (class "Default")
      (node (ref "R2") (pin "1") (pinfunction "1_1") (pintype "passive"))
      (node (ref "U4") (pin "12") (pinfunction "VOUT_12") (pintype "output"))
    )
    (net (code "72") (name "Net-(U4-VREF)") (class "Default")
      (node (ref "C16") (pin "2") (pinfunction "2_2") (pintype "passive"))
      (node (ref "C18") (pin "2") (pinfunction "2_2") (pintype "passive"))
      (node (ref "C23") (pin "+") (pinfunction "+_+") (pintype "passive"))
      (node (ref "C26") (pin "+") (pinfunction "+_+") (pintype "passive"))
      (node (ref "U4") (pin "9") (pinfunction "VREF_9") (pintype "input"))
      (node (ref "U5") (pin "9") (pinfunction "REFP0_9") (pintype "bidirectional"))
      (node (ref "U6") (pin "5") (pinfunction "OUT_S_5") (pintype "input"))
      (node (ref "U6") (pin "6") (pinfunction "OUT_F_6") (pintype "power_in"))
    )
    (net (code "73") (name "Net-(U5-AIN0{slash}REFP1)") (class "Default")
      (node (ref "R2") (pin "2") (pinfunction "2_2") (pintype "passive"))
      (node (ref "U5") (pin "11") (pinfunction "AIN0/REFP1_11") (pintype "bidirectional"))
    )
    (net (code "74") (name "Net-(U5-AIN1)") (class "Default")
      (node (ref "R3") (pin "2") (pinfunction "2_2") (pintype "passive"))
      (node (ref "U5") (pin "10") (pinfunction "AIN1_10") (pintype "bidirectional"))
    )
    (net (code "75") (name "Net-(U5-DIN)") (class "Default")
      (node (ref "JP1") (pin "2") (pinfunction "2_2") (pintype "passive"))
      (node (ref "U5") (pin "16") (pinfunction "DIN_16") (pintype "bidirectional"))
    )
    (net (code "76") (name "Net-(U5-DOUT{slash}~{DRDY})") (class "Default")
      (node (ref "JP1") (pin "1") (pinfunction "1_1") (pintype "passive"))
      (node (ref "U5") (pin "15") (pinfunction "DOUT/~{DRDY}_15") (pintype "bidirectional"))
    )
    (net (code "77") (name "Net-(U5-SCLK)") (class "Default")
      (node (ref "JP1") (pin "3") (pinfunction "3_3") (pintype "passive"))
      (node (ref "U5") (pin "1") (pinfunction "SCLK_1") (pintype "bidirectional"))
    )
    (net (code "78") (name "Net-(U5-~{CS})") (class "Default")
      (node (ref "JP1") (pin "4") (pinfunction "4_4") (pintype "passive"))
      (node (ref "U5") (pin "2") (pinfunction "~{CS}_2") (pintype "bidirectional"))
    )
    (net (code "79") (name "Net-(U5-~{DRDY})") (class "Default")
      (node (ref "JP1") (pin "5") (pinfunction "5_5") (pintype "passive"))
      (node (ref "U5") (pin "14") (pinfunction "~{DRDY}_14") (pintype "bidirectional"))
    )
    (net (code "80") (name "unconnected-(U1-1_NC-Pad12)") (class "Default")
      (node (ref "U1") (pin "12") (pinfunction "1_NC_12") (pintype "passive"))
    )
    (net (code "81") (name "unconnected-(U1-2_NC-Pad13)") (class "Default")
      (node (ref "U1") (pin "13") (pinfunction "2_NC_13") (pintype "passive"))
    )
    (net (code "82") (name "unconnected-(U2-1_NC-Pad12)") (class "Default")
      (node (ref "U2") (pin "12") (pinfunction "1_NC_12") (pintype "passive"))
    )
    (net (code "83") (name "unconnected-(U2-2_NC-Pad13)") (class "Default")
      (node (ref "U2") (pin "13") (pinfunction "2_NC_13") (pintype "passive"))
    )
    (net (code "84") (name "unconnected-(U3-1_NC-Pad12)") (class "Default")
      (node (ref "U3") (pin "12") (pinfunction "1_NC_12") (pintype "passive"))
    )
    (net (code "85") (name "unconnected-(U3-2_NC-Pad13)") (class "Default")
      (node (ref "U3") (pin "13") (pinfunction "2_NC_13") (pintype "passive"))
    )
    (net (code "86") (name "unconnected-(U4-CS_N-Pad14)") (class "Default")
      (node (ref "U4") (pin "14") (pinfunction "CS_N_14") (pintype "input"))
    )
    (net (code "87") (name "unconnected-(U4-SCLK-Pad15)") (class "Default")
      (node (ref "U4") (pin "15") (pinfunction "SCLK_15") (pintype "input"))
    )
    (net (code "88") (name "unconnected-(U4-SDI-Pad16)") (class "Default")
      (node (ref "U4") (pin "16") (pinfunction "SDI_16") (pintype "input"))
    )
    (net (code "89") (name "unconnected-(U4-SDO_DIAG-Pad13)") (class "Default")
      (node (ref "U4") (pin "13") (pinfunction "SDO_DIAG_13") (pintype "bidirectional"))
    )
    (net (code "90") (name "unconnected-(U4-VCMHI-Pad7)") (class "Default")
      (node (ref "U4") (pin "7") (pinfunction "VCMHI_7") (pintype "tri_state"))
    )
    (net (code "91") (name "unconnected-(U5-AIN2-Pad7)") (class "Default")
      (node (ref "U5") (pin "7") (pinfunction "AIN2_7") (pintype "bidirectional"))
    )
    (net (code "92") (name "unconnected-(U5-AIN3{slash}REFN1-Pad6)") (class "Default")
      (node (ref "U5") (pin "6") (pinfunction "AIN3/REFN1_6") (pintype "bidirectional"))
    )
  )
)
